# Practicum_update.net
KiCad netlist of a schematic drawn in EAGLE
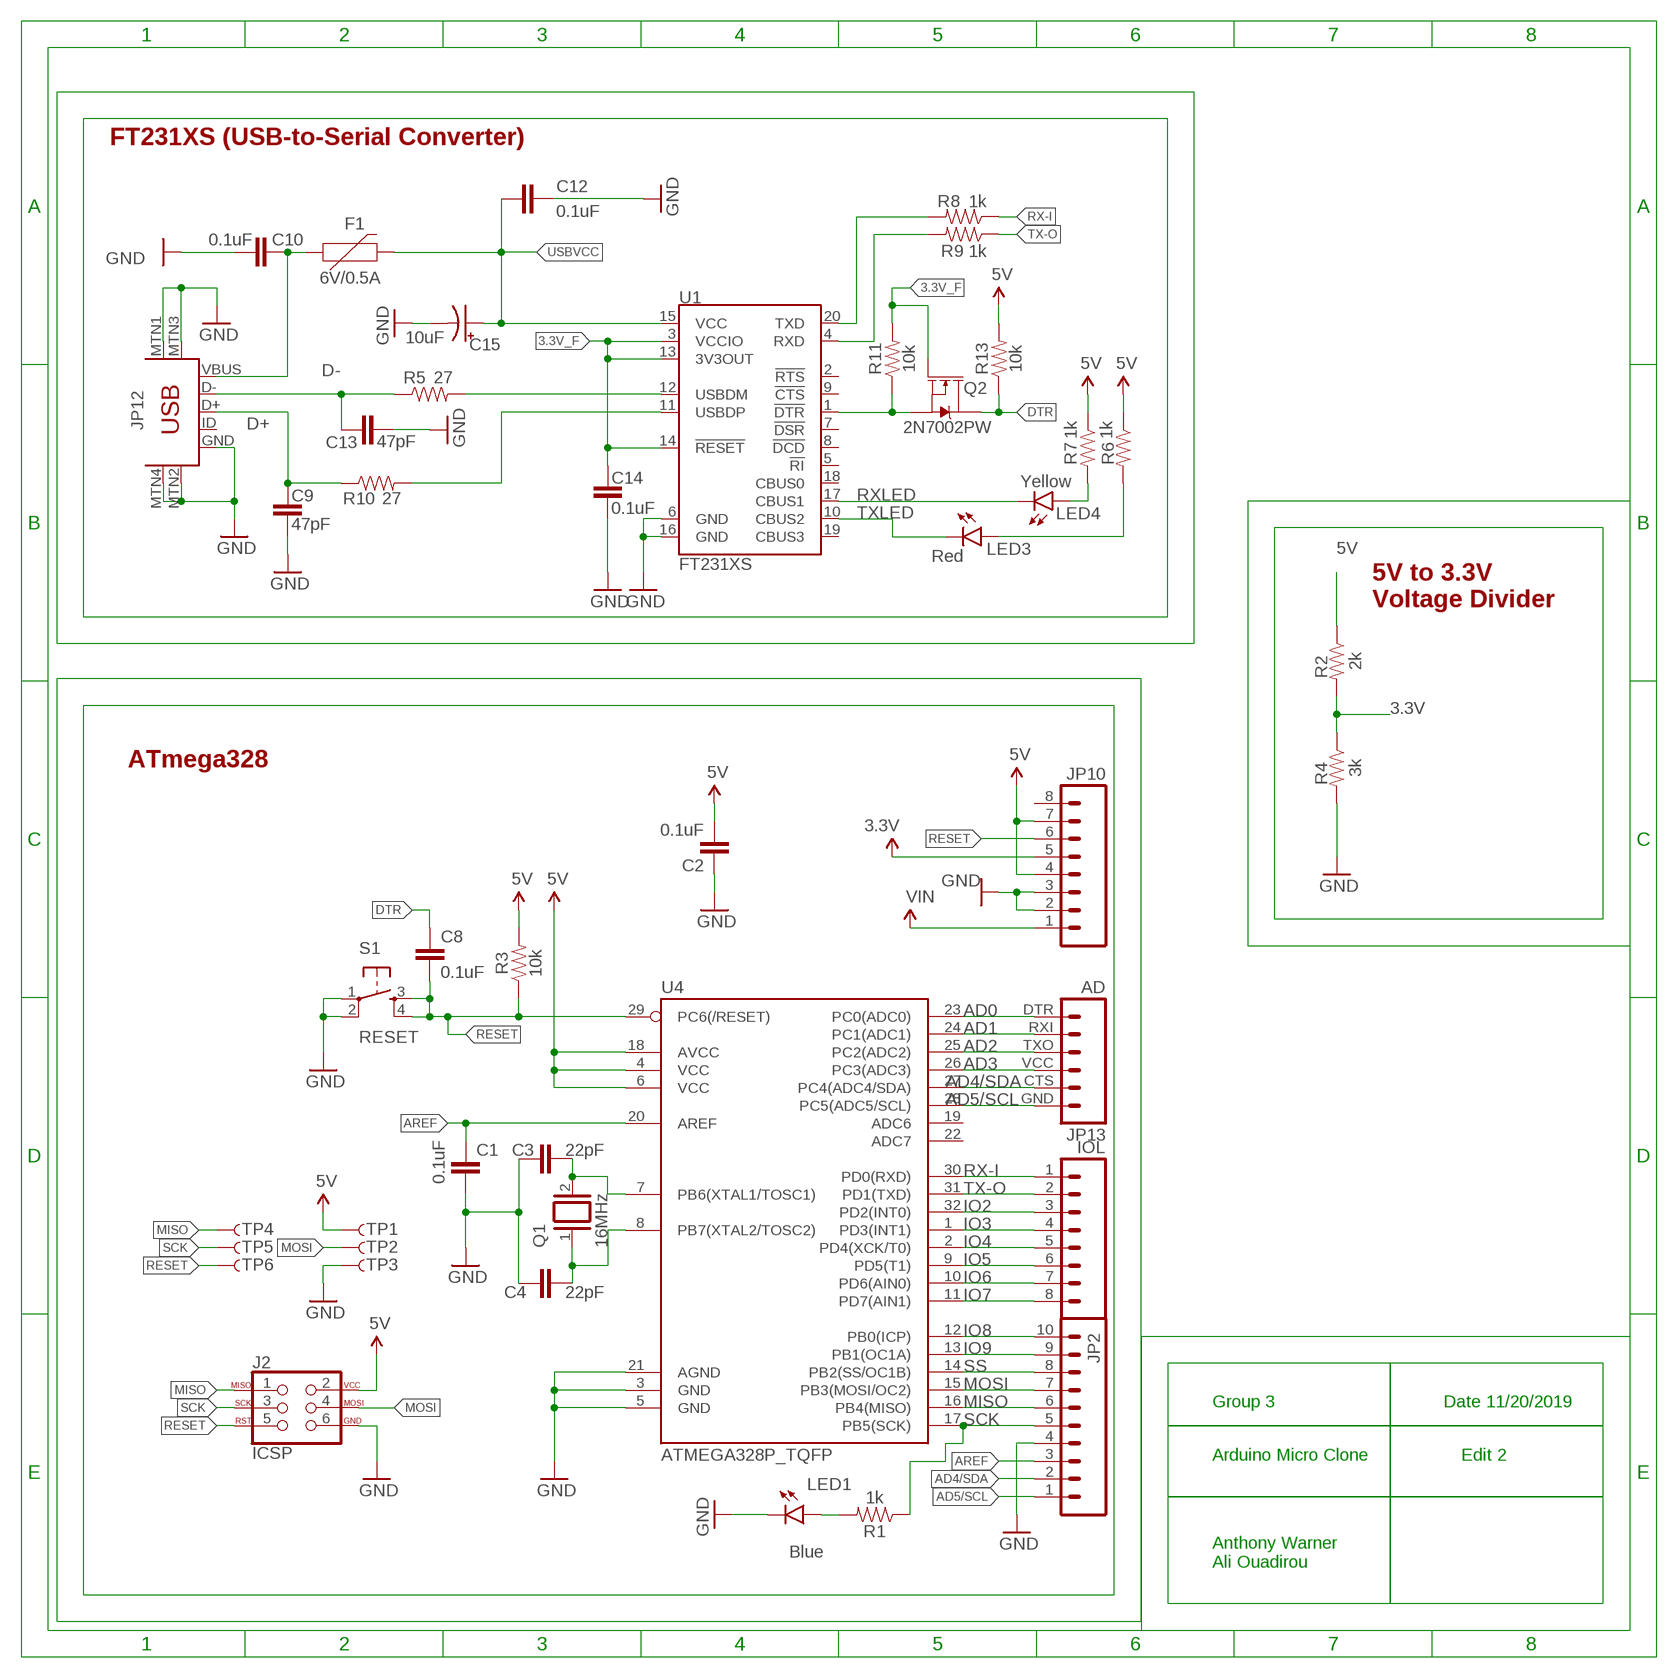
[diagram p0: schematic, sheet 1]

(export (version "E")
  (design (tool "Eeschema 10.0.6"))
  (components
    (comp (ref "C1")
      (value "0.1uF")
      (footprint "eagle-import:0603")
      (libsource (lib "eagle-import") (part "0.1UF-0603-25V-(+80/-20%)"))
    )
    (comp (ref "C2")
      (value "0.1uF")
      (footprint "eagle-import:0603")
      (libsource (lib "eagle-import") (part "0.1UF-0603-25V-(+80/-20%)"))
    )
    (comp (ref "C3")
      (value "22pF")
      (footprint "eagle-import:0603")
      (libsource (lib "eagle-import") (part "0.1UF-0603-25V-(+80/-20%)"))
    )
    (comp (ref "C4")
      (value "22pF")
      (footprint "eagle-import:0603")
      (libsource (lib "eagle-import") (part "0.1UF-0603-25V-(+80/-20%)"))
    )
    (comp (ref "C8")
      (value "0.1uF")
      (footprint "eagle-import:0603")
      (libsource (lib "eagle-import") (part "0.1UF-0603-25V-(+80/-20%)"))
    )
    (comp (ref "C9")
      (value "47pF")
      (footprint "eagle-import:0603")
      (libsource (lib "eagle-import") (part "47PF-0603-50V-5%"))
    )
    (comp (ref "C10")
      (value "0.1uF")
      (footprint "eagle-import:0603")
      (libsource (lib "eagle-import") (part "0.1UF-0603-25V-(+80/-20%)"))
    )
    (comp (ref "C12")
      (value "0.1uF")
      (footprint "eagle-import:0603")
      (libsource (lib "eagle-import") (part "0.1UF-0603-25V-(+80/-20%)"))
    )
    (comp (ref "C13")
      (value "47pF")
      (footprint "eagle-import:0603")
      (libsource (lib "eagle-import") (part "47PF-0603-50V-5%"))
    )
    (comp (ref "C14")
      (value "0.1uF")
      (footprint "eagle-import:0603")
      (libsource (lib "eagle-import") (part "0.1UF-0603-25V-(+80/-20%)"))
    )
    (comp (ref "C15")
      (value "10uF")
      (footprint "eagle-import:EIA3216")
      (libsource (lib "eagle-import") (part "10UF-POLAR-EIA3216-16V-10%(TANT)"))
    )
    (comp (ref "F1")
      (value "6V/0.5A")
      (footprint "eagle-import:1206")
      (libsource (lib "eagle-import") (part "PTC-HALF_AMP"))
    )
    (comp (ref "J2")
      (value "ICSP")
      (footprint "eagle-import:2X3-NS")
      (libsource (lib "eagle-import") (part "AVR_SPI_PROG_3X2NS"))
    )
    (comp (ref "JP2")
      (value "M10\"")
      (footprint "eagle-import:1X10")
      (libsource (lib "eagle-import") (part "M10{dblquote}"))
    )
    (comp (ref "JP10")
      (value "M081X08")
      (footprint "eagle-import:1X08")
      (libsource (lib "eagle-import") (part "M081X08"))
    )
    (comp (ref "JP11")
      (value "IOL")
      (footprint "eagle-import:1X08")
      (libsource (lib "eagle-import") (part "M081X08"))
    )
    (comp (ref "JP12")
      (value "USB-MINIB-5PIN")
      (footprint "eagle-import:USB-MINIB")
      (libsource (lib "eagle-import") (part "USB-MINIB-5PIN"))
    )
    (comp (ref "JP13")
      (value "AD")
      (footprint "eagle-import:1X06")
      (libsource (lib "eagle-import") (part "M06SIP"))
    )
    (comp (ref "LED1")
      (value "Blue")
      (footprint "eagle-import:LED-1206")
      (libsource (lib "eagle-import") (part "LED1206"))
    )
    (comp (ref "LED3")
      (value "Red")
      (footprint "eagle-import:LED-1206")
      (libsource (lib "eagle-import") (part "LED1206"))
    )
    (comp (ref "LED4")
      (value "Yellow")
      (footprint "eagle-import:LED-1206")
      (libsource (lib "eagle-import") (part "LED1206"))
    )
    (comp (ref "Q1")
      (value "16MHz")
      (footprint "eagle-import:QS")
      (libsource (lib "eagle-import") (part "XTAL/S"))
    )
    (comp (ref "Q2")
      (value "2N7002PW")
      (footprint "eagle-import:SOT323")
      (libsource (lib "eagle-import") (part "MOSFET-NCH-2N7002PW"))
    )
    (comp (ref "R1")
      (value "1k")
      (footprint "eagle-import:0603")
      (libsource (lib "eagle-import") (part "1KOHM-0603-1/10W-1%"))
    )
    (comp (ref "R2")
      (value "2k")
      (footprint "eagle-import:0603")
      (libsource (lib "eagle-import") (part "1KOHM-0603-1/10W-1%"))
    )
    (comp (ref "R3")
      (value "10k")
      (footprint "eagle-import:0603")
      (libsource (lib "eagle-import") (part "10KOHM-0603-1/10W-1%"))
    )
    (comp (ref "R4")
      (value "3k")
      (footprint "eagle-import:0603")
      (libsource (lib "eagle-import") (part "1KOHM-0603-1/10W-1%"))
    )
    (comp (ref "R5")
      (value "27")
      (footprint "eagle-import:0603")
      (libsource (lib "eagle-import") (part "27OHM-0603-1/10W-1%"))
    )
    (comp (ref "R6")
      (value "1k")
      (footprint "eagle-import:0603")
      (libsource (lib "eagle-import") (part "1KOHM-0603-1/10W-1%"))
    )
    (comp (ref "R7")
      (value "1k")
      (footprint "eagle-import:0603")
      (libsource (lib "eagle-import") (part "1KOHM-0603-1/10W-1%"))
    )
    (comp (ref "R8")
      (value "1k")
      (footprint "eagle-import:0603")
      (libsource (lib "eagle-import") (part "1KOHM-0603-1/10W-1%"))
    )
    (comp (ref "R9")
      (value "1k")
      (footprint "eagle-import:0603")
      (libsource (lib "eagle-import") (part "1KOHM-0603-1/10W-1%"))
    )
    (comp (ref "R10")
      (value "27")
      (footprint "eagle-import:0603")
      (libsource (lib "eagle-import") (part "27OHM-0603-1/10W-1%"))
    )
    (comp (ref "R11")
      (value "10k")
      (footprint "eagle-import:0603")
      (libsource (lib "eagle-import") (part "10KOHM-0603-1/10W-1%"))
    )
    (comp (ref "R13")
      (value "10k")
      (footprint "eagle-import:0603")
      (libsource (lib "eagle-import") (part "10KOHM-0603-1/10W-1%"))
    )
    (comp (ref "S1")
      (value "RESET")
      (footprint "eagle-import:TACTILE-SWITCH-SMD")
      (libsource (lib "eagle-import") (part "SWITCH_SPST_4_PINSQUARE"))
    )
    (comp (ref "TP1")
      (value "TP-3x5")
      (footprint "eagle-import:PAD.03X.05")
      (libsource (lib "eagle-import") (part "TEST-POINT3X5"))
    )
    (comp (ref "TP2")
      (value "TP-3x5")
      (footprint "eagle-import:PAD.03X.05")
      (libsource (lib "eagle-import") (part "TEST-POINT3X5"))
    )
    (comp (ref "TP3")
      (value "TP-3x5")
      (footprint "eagle-import:PAD.03X.05")
      (libsource (lib "eagle-import") (part "TEST-POINT3X5"))
    )
    (comp (ref "TP4")
      (value "TP-3x5")
      (footprint "eagle-import:PAD.03X.05")
      (libsource (lib "eagle-import") (part "TEST-POINT3X5"))
    )
    (comp (ref "TP5")
      (value "TP-3x5")
      (footprint "eagle-import:PAD.03X.05")
      (libsource (lib "eagle-import") (part "SparkFun-Passives_TEST-POINT3X5"))
    )
    (comp (ref "TP6")
      (value "TP-3x5")
      (footprint "eagle-import:PAD.03X.05")
      (libsource (lib "eagle-import") (part "TEST-POINT3X5"))
    )
    (comp (ref "U1")
      (value "FT231XS")
      (footprint "eagle-import:SSOP20_L")
      (libsource (lib "eagle-import") (part "FT231XS"))
    )
    (comp (ref "U4")
      (value "ATMEGA328P_TQFP")
      (footprint "eagle-import:TQFP32-08")
      (libsource (lib "eagle-import") (part "ATMEGA328P_TQFP"))
    )
  )
  (nets
    (net (code "1") (name "/AD0") (class "Default")
      (node (ref "JP13") (pin "DTR") (pinfunction "1_DTR") (pintype "passive"))
      (node (ref "U4") (pin "23") (pinfunction "PC0(ADC0)_23") (pintype "bidirectional"))
    )
    (net (code "2") (name "/AD1") (class "Default")
      (node (ref "JP13") (pin "RXI") (pinfunction "2_RXI") (pintype "passive"))
      (node (ref "U4") (pin "24") (pinfunction "PC1(ADC1)_24") (pintype "bidirectional"))
    )
    (net (code "3") (name "/AD2") (class "Default")
      (node (ref "JP13") (pin "TXO") (pinfunction "3_TXO") (pintype "passive"))
      (node (ref "U4") (pin "25") (pinfunction "PC2(ADC2)_25") (pintype "bidirectional"))
    )
    (net (code "4") (name "/AD3") (class "Default")
      (node (ref "JP13") (pin "VCC") (pinfunction "4_VCC") (pintype "passive"))
      (node (ref "U4") (pin "26") (pinfunction "PC3(ADC3)_26") (pintype "bidirectional"))
    )
    (net (code "5") (name "/D+") (class "Default")
      (node (ref "C9") (pin "1") (pinfunction "1_1") (pintype "passive"))
      (node (ref "JP12") (pin "D+") (pinfunction "D+_D+") (pintype "bidirectional"))
      (node (ref "R10") (pin "1") (pinfunction "1_1") (pintype "passive"))
    )
    (net (code "6") (name "/D-") (class "Default")
      (node (ref "C13") (pin "1") (pinfunction "1_1") (pintype "passive"))
      (node (ref "JP12") (pin "D-") (pinfunction "D-_D-") (pintype "bidirectional"))
      (node (ref "R5") (pin "1") (pinfunction "1_1") (pintype "passive"))
    )
    (net (code "7") (name "/IO2") (class "Default")
      (node (ref "JP11") (pin "3") (pinfunction "3_3") (pintype "passive"))
      (node (ref "U4") (pin "32") (pinfunction "PD2(INT0)_32") (pintype "bidirectional"))
    )
    (net (code "8") (name "/IO3") (class "Default")
      (node (ref "JP11") (pin "4") (pinfunction "4_4") (pintype "passive"))
      (node (ref "U4") (pin "1") (pinfunction "PD3(INT1)_1") (pintype "bidirectional"))
    )
    (net (code "9") (name "/IO4") (class "Default")
      (node (ref "JP11") (pin "5") (pinfunction "5_5") (pintype "passive"))
      (node (ref "U4") (pin "2") (pinfunction "PD4(XCK/T0)_2") (pintype "bidirectional"))
    )
    (net (code "10") (name "/IO5") (class "Default")
      (node (ref "JP11") (pin "6") (pinfunction "6_6") (pintype "passive"))
      (node (ref "U4") (pin "9") (pinfunction "PD5(T1)_9") (pintype "bidirectional"))
    )
    (net (code "11") (name "/IO6") (class "Default")
      (node (ref "JP11") (pin "7") (pinfunction "7_7") (pintype "passive"))
      (node (ref "U4") (pin "10") (pinfunction "PD6(AIN0)_10") (pintype "bidirectional"))
    )
    (net (code "12") (name "/IO7") (class "Default")
      (node (ref "JP11") (pin "8") (pinfunction "8_8") (pintype "passive"))
      (node (ref "U4") (pin "11") (pinfunction "PD7(AIN1)_11") (pintype "bidirectional"))
    )
    (net (code "13") (name "/IO8") (class "Default")
      (node (ref "JP2") (pin "10") (pinfunction "10_10") (pintype "passive"))
      (node (ref "U4") (pin "12") (pinfunction "PB0(ICP)_12") (pintype "bidirectional"))
    )
    (net (code "14") (name "/IO9") (class "Default")
      (node (ref "JP2") (pin "9") (pinfunction "9_9") (pintype "passive"))
      (node (ref "U4") (pin "13") (pinfunction "PB1(OC1A)_13") (pintype "bidirectional"))
    )
    (net (code "15") (name "/RXLED") (class "Default")
      (node (ref "LED4") (pin "C") (pinfunction "C_C") (pintype "passive"))
      (node (ref "U1") (pin "17") (pinfunction "CBUS1_17") (pintype "bidirectional"))
    )
    (net (code "16") (name "/SS") (class "Default")
      (node (ref "JP2") (pin "8") (pinfunction "8_8") (pintype "passive"))
      (node (ref "U4") (pin "14") (pinfunction "PB2(SS/OC1B)_14") (pintype "bidirectional"))
    )
    (net (code "17") (name "/TXLED") (class "Default")
      (node (ref "LED3") (pin "C") (pinfunction "C_C") (pintype "passive"))
      (node (ref "U1") (pin "10") (pinfunction "CBUS2_10") (pintype "bidirectional"))
    )
    (net (code "18") (name "3.3V") (class "Default")
      (node (ref "JP10") (pin "5") (pinfunction "5_5") (pintype "passive"))
      (node (ref "R2") (pin "2") (pinfunction "2_2") (pintype "passive"))
      (node (ref "R4") (pin "1") (pinfunction "1_1") (pintype "passive"))
    )
    (net (code "19") (name "3.3V_F") (class "Default")
      (node (ref "C14") (pin "1") (pinfunction "1_1") (pintype "passive"))
      (node (ref "Q2") (pin "1") (pinfunction "G_1") (pintype "bidirectional"))
      (node (ref "R11") (pin "2") (pinfunction "2_2") (pintype "passive"))
      (node (ref "U1") (pin "13") (pinfunction "3V3OUT_13") (pintype "bidirectional"))
      (node (ref "U1") (pin "14") (pinfunction "~{RESET}_14") (pintype "bidirectional"))
      (node (ref "U1") (pin "3") (pinfunction "VCCIO_3") (pintype "bidirectional"))
    )
    (net (code "20") (name "5V") (class "Default")
      (node (ref "C2") (pin "2") (pinfunction "2_2") (pintype "passive"))
      (node (ref "J2") (pin "2") (pinfunction "2_2") (pintype "passive"))
      (node (ref "JP10") (pin "4") (pinfunction "4_4") (pintype "passive"))
      (node (ref "JP10") (pin "7") (pinfunction "7_7") (pintype "passive"))
      (node (ref "R13") (pin "2") (pinfunction "2_2") (pintype "passive"))
      (node (ref "R2") (pin "1") (pinfunction "1_1") (pintype "passive"))
      (node (ref "R3") (pin "2") (pinfunction "2_2") (pintype "passive"))
      (node (ref "R6") (pin "1") (pinfunction "1_1") (pintype "passive"))
      (node (ref "R7") (pin "1") (pinfunction "1_1") (pintype "passive"))
      (node (ref "TP1") (pin "P$1") (pinfunction "1_P$1") (pintype "bidirectional"))
      (node (ref "U4") (pin "18") (pinfunction "AVCC_18") (pintype "bidirectional"))
      (node (ref "U4") (pin "4") (pinfunction "VCC_4") (pintype "bidirectional"))
      (node (ref "U4") (pin "6") (pinfunction "VCC_6") (pintype "bidirectional"))
    )
    (net (code "21") (name "AD4{slash}SDA") (class "Default")
      (node (ref "JP13") (pin "CTS") (pinfunction "5_CTS") (pintype "passive"))
      (node (ref "JP2") (pin "2") (pinfunction "2_2") (pintype "passive"))
      (node (ref "U4") (pin "27") (pinfunction "PC4(ADC4/SDA)_27") (pintype "bidirectional"))
    )
    (net (code "22") (name "AD5{slash}SCL") (class "Default")
      (node (ref "JP13") (pin "GND") (pinfunction "6_GND") (pintype "passive"))
      (node (ref "JP2") (pin "1") (pinfunction "1_1") (pintype "passive"))
      (node (ref "U4") (pin "28") (pinfunction "PC5(ADC5/SCL)_28") (pintype "bidirectional"))
    )
    (net (code "23") (name "AREF") (class "Default")
      (node (ref "C1") (pin "1") (pinfunction "1_1") (pintype "passive"))
      (node (ref "JP2") (pin "3") (pinfunction "3_3") (pintype "passive"))
      (node (ref "U4") (pin "20") (pinfunction "AREF_20") (pintype "bidirectional"))
    )
    (net (code "24") (name "DTR") (class "Default")
      (node (ref "C8") (pin "1") (pinfunction "1_1") (pintype "passive"))
      (node (ref "Q2") (pin "3") (pinfunction "D_3") (pintype "bidirectional"))
      (node (ref "R13") (pin "1") (pinfunction "1_1") (pintype "passive"))
    )
    (net (code "25") (name "GND") (class "Default")
      (node (ref "C1") (pin "2") (pinfunction "2_2") (pintype "passive"))
      (node (ref "C10") (pin "2") (pinfunction "2_2") (pintype "passive"))
      (node (ref "C12") (pin "2") (pinfunction "2_2") (pintype "passive"))
      (node (ref "C13") (pin "2") (pinfunction "2_2") (pintype "passive"))
      (node (ref "C14") (pin "2") (pinfunction "2_2") (pintype "passive"))
      (node (ref "C15") (pin "-") (pinfunction "-_-") (pintype "passive"))
      (node (ref "C2") (pin "1") (pinfunction "1_1") (pintype "passive"))
      (node (ref "C3") (pin "1") (pinfunction "1_1") (pintype "passive"))
      (node (ref "C4") (pin "1") (pinfunction "1_1") (pintype "passive"))
      (node (ref "C9") (pin "2") (pinfunction "2_2") (pintype "passive"))
      (node (ref "J2") (pin "6") (pinfunction "6_6") (pintype "passive"))
      (node (ref "JP10") (pin "2") (pinfunction "2_2") (pintype "passive"))
      (node (ref "JP10") (pin "3") (pinfunction "3_3") (pintype "passive"))
      (node (ref "JP12") (pin "GND") (pinfunction "GND_GND") (pintype "bidirectional"))
      (node (ref "JP12") (pin "MTN1") (pinfunction "MTN2_MTN1") (pintype "bidirectional"))
      (node (ref "JP12") (pin "MTN2") (pinfunction "MTN3_MTN2") (pintype "bidirectional"))
      (node (ref "JP12") (pin "MTN3") (pinfunction "MTN1_MTN3") (pintype "bidirectional"))
      (node (ref "JP12") (pin "MTN4") (pinfunction "MTN4_MTN4") (pintype "bidirectional"))
      (node (ref "JP2") (pin "4") (pinfunction "4_4") (pintype "passive"))
      (node (ref "LED1") (pin "C") (pinfunction "C_C") (pintype "passive"))
      (node (ref "R4") (pin "2") (pinfunction "2_2") (pintype "passive"))
      (node (ref "S1") (pin "1") (pinfunction "1_1") (pintype "passive"))
      (node (ref "S1") (pin "2") (pinfunction "2_2") (pintype "passive"))
      (node (ref "TP3") (pin "P$1") (pinfunction "1_P$1") (pintype "bidirectional"))
      (node (ref "U1") (pin "16") (pinfunction "GND_16") (pintype "bidirectional"))
      (node (ref "U1") (pin "6") (pinfunction "GND_6") (pintype "bidirectional"))
      (node (ref "U4") (pin "21") (pinfunction "AGND_21") (pintype "bidirectional"))
      (node (ref "U4") (pin "3") (pinfunction "GND_3") (pintype "bidirectional"))
      (node (ref "U4") (pin "5") (pinfunction "GND_5") (pintype "bidirectional"))
    )
    (net (code "26") (name "MISO") (class "Default")
      (node (ref "J2") (pin "1") (pinfunction "1_1") (pintype "passive"))
      (node (ref "JP2") (pin "6") (pinfunction "6_6") (pintype "passive"))
      (node (ref "TP4") (pin "P$1") (pinfunction "1_P$1") (pintype "bidirectional"))
      (node (ref "U4") (pin "16") (pinfunction "PB4(MISO)_16") (pintype "bidirectional"))
    )
    (net (code "27") (name "MOSI") (class "Default")
      (node (ref "J2") (pin "4") (pinfunction "4_4") (pintype "passive"))
      (node (ref "JP2") (pin "7") (pinfunction "7_7") (pintype "passive"))
      (node (ref "TP2") (pin "P$1") (pinfunction "1_P$1") (pintype "bidirectional"))
      (node (ref "U4") (pin "15") (pinfunction "PB3(MOSI/OC2)_15") (pintype "bidirectional"))
    )
    (net (code "28") (name "Net-(C10-Pad1)") (class "Default")
      (node (ref "C10") (pin "1") (pinfunction "1_1") (pintype "passive"))
      (node (ref "F1") (pin "1") (pinfunction "1_1") (pintype "bidirectional"))
      (node (ref "JP12") (pin "VBUS") (pinfunction "VBUS_VBUS") (pintype "bidirectional"))
    )
    (net (code "29") (name "Net-(LED1-PadA)") (class "Default")
      (node (ref "LED1") (pin "A") (pinfunction "A_A") (pintype "passive"))
      (node (ref "R1") (pin "2") (pinfunction "2_2") (pintype "passive"))
    )
    (net (code "30") (name "Net-(LED3-PadA)") (class "Default")
      (node (ref "LED3") (pin "A") (pinfunction "A_A") (pintype "passive"))
      (node (ref "R6") (pin "2") (pinfunction "2_2") (pintype "passive"))
    )
    (net (code "31") (name "Net-(LED4-PadA)") (class "Default")
      (node (ref "LED4") (pin "A") (pinfunction "A_A") (pintype "passive"))
      (node (ref "R7") (pin "2") (pinfunction "2_2") (pintype "passive"))
    )
    (net (code "32") (name "Net-(Q2-S)") (class "Default")
      (node (ref "Q2") (pin "2") (pinfunction "S_2") (pintype "bidirectional"))
      (node (ref "R11") (pin "1") (pinfunction "1_1") (pintype "passive"))
      (node (ref "U1") (pin "1") (pinfunction "~{DTR}_1") (pintype "bidirectional"))
    )
    (net (code "33") (name "Net-(U1-RXD)") (class "Default")
      (node (ref "R9") (pin "2") (pinfunction "2_2") (pintype "passive"))
      (node (ref "U1") (pin "4") (pinfunction "RXD_4") (pintype "bidirectional"))
    )
    (net (code "34") (name "Net-(U1-TXD)") (class "Default")
      (node (ref "R8") (pin "2") (pinfunction "2_2") (pintype "passive"))
      (node (ref "U1") (pin "20") (pinfunction "TXD_20") (pintype "bidirectional"))
    )
    (net (code "35") (name "Net-(U1-USBDM)") (class "Default")
      (node (ref "R5") (pin "2") (pinfunction "2_2") (pintype "passive"))
      (node (ref "U1") (pin "12") (pinfunction "USBDM_12") (pintype "bidirectional"))
    )
    (net (code "36") (name "Net-(U1-USBDP)") (class "Default")
      (node (ref "R10") (pin "2") (pinfunction "2_2") (pintype "passive"))
      (node (ref "U1") (pin "11") (pinfunction "USBDP_11") (pintype "bidirectional"))
    )
    (net (code "37") (name "Net-(U4-PB6(XTAL1{slash}TOSC1))") (class "Default")
      (node (ref "C3") (pin "2") (pinfunction "2_2") (pintype "passive"))
      (node (ref "Q1") (pin "2") (pinfunction "2_2") (pintype "passive"))
      (node (ref "U4") (pin "7") (pinfunction "PB6(XTAL1/TOSC1)_7") (pintype "bidirectional"))
    )
    (net (code "38") (name "Net-(U4-PB7(XTAL2{slash}TOSC2))") (class "Default")
      (node (ref "C4") (pin "2") (pinfunction "2_2") (pintype "passive"))
      (node (ref "Q1") (pin "1") (pinfunction "1_1") (pintype "passive"))
      (node (ref "U4") (pin "8") (pinfunction "PB7(XTAL2/TOSC2)_8") (pintype "bidirectional"))
    )
    (net (code "39") (name "RESET") (class "Default")
      (node (ref "C8") (pin "2") (pinfunction "2_2") (pintype "passive"))
      (node (ref "J2") (pin "5") (pinfunction "5_5") (pintype "passive"))
      (node (ref "JP10") (pin "6") (pinfunction "6_6") (pintype "passive"))
      (node (ref "R3") (pin "1") (pinfunction "1_1") (pintype "passive"))
      (node (ref "S1") (pin "3") (pinfunction "3_3") (pintype "passive"))
      (node (ref "S1") (pin "4") (pinfunction "4_4") (pintype "passive"))
      (node (ref "TP6") (pin "P$1") (pinfunction "1_P$1") (pintype "bidirectional"))
      (node (ref "U4") (pin "29") (pinfunction "PC6(/RESET)_29") (pintype "bidirectional"))
    )
    (net (code "40") (name "RX-I") (class "Default")
      (node (ref "JP11") (pin "1") (pinfunction "1_1") (pintype "passive"))
      (node (ref "R8") (pin "1") (pinfunction "1_1") (pintype "passive"))
      (node (ref "U4") (pin "30") (pinfunction "PD0(RXD)_30") (pintype "bidirectional"))
    )
    (net (code "41") (name "SCK") (class "Default")
      (node (ref "J2") (pin "3") (pinfunction "3_3") (pintype "passive"))
      (node (ref "JP2") (pin "5") (pinfunction "5_5") (pintype "passive"))
      (node (ref "R1") (pin "1") (pinfunction "1_1") (pintype "passive"))
      (node (ref "TP5") (pin "P$1") (pinfunction "1_P$1") (pintype "bidirectional"))
      (node (ref "U4") (pin "17") (pinfunction "PB5(SCK)_17") (pintype "bidirectional"))
    )
    (net (code "42") (name "TX-O") (class "Default")
      (node (ref "JP11") (pin "2") (pinfunction "2_2") (pintype "passive"))
      (node (ref "R9") (pin "1") (pinfunction "1_1") (pintype "passive"))
      (node (ref "U4") (pin "31") (pinfunction "PD1(TXD)_31") (pintype "bidirectional"))
    )
    (net (code "43") (name "USBVCC") (class "Default")
      (node (ref "C12") (pin "1") (pinfunction "1_1") (pintype "passive"))
      (node (ref "C15") (pin "+") (pinfunction "+_+") (pintype "passive"))
      (node (ref "F1") (pin "2") (pinfunction "2_2") (pintype "bidirectional"))
      (node (ref "U1") (pin "15") (pinfunction "VCC_15") (pintype "bidirectional"))
    )
    (net (code "44") (name "VIN") (class "Default")
      (node (ref "JP10") (pin "1") (pinfunction "1_1") (pintype "passive"))
    )
    (net (code "45") (name "unconnected-(JP10-Pad8)") (class "Default")
      (node (ref "JP10") (pin "8") (pinfunction "8_8") (pintype "passive"))
    )
    (net (code "46") (name "unconnected-(JP12-PadID)") (class "Default")
      (node (ref "JP12") (pin "ID") (pinfunction "ID_ID") (pintype "bidirectional"))
    )
    (net (code "47") (name "unconnected-(U1-CBUS0-Pad18)") (class "Default")
      (node (ref "U1") (pin "18") (pinfunction "CBUS0_18") (pintype "bidirectional"))
    )
    (net (code "48") (name "unconnected-(U1-CBUS3-Pad19)") (class "Default")
      (node (ref "U1") (pin "19") (pinfunction "CBUS3_19") (pintype "bidirectional"))
    )
    (net (code "49") (name "unconnected-(U1-~{CTS}-Pad9)") (class "Default")
      (node (ref "U1") (pin "9") (pinfunction "~{CTS}_9") (pintype "bidirectional"))
    )
    (net (code "50") (name "unconnected-(U1-~{DCD}-Pad8)") (class "Default")
      (node (ref "U1") (pin "8") (pinfunction "~{DCD}_8") (pintype "bidirectional"))
    )
    (net (code "51") (name "unconnected-(U1-~{DSR}-Pad7)") (class "Default")
      (node (ref "U1") (pin "7") (pinfunction "~{DSR}_7") (pintype "bidirectional"))
    )
    (net (code "52") (name "unconnected-(U1-~{RI}-Pad5)") (class "Default")
      (node (ref "U1") (pin "5") (pinfunction "~{RI}_5") (pintype "bidirectional"))
    )
    (net (code "53") (name "unconnected-(U1-~{RTS}-Pad2)") (class "Default")
      (node (ref "U1") (pin "2") (pinfunction "~{RTS}_2") (pintype "bidirectional"))
    )
    (net (code "54") (name "unconnected-(U4-ADC6-Pad19)") (class "Default")
      (node (ref "U4") (pin "19") (pinfunction "ADC6_19") (pintype "bidirectional"))
    )
    (net (code "55") (name "unconnected-(U4-ADC7-Pad22)") (class "Default")
      (node (ref "U4") (pin "22") (pinfunction "ADC7_22") (pintype "bidirectional"))
    )
  )
)
